# USB_connnection.net
KiCad netlist of a schematic drawn in Altium Designer
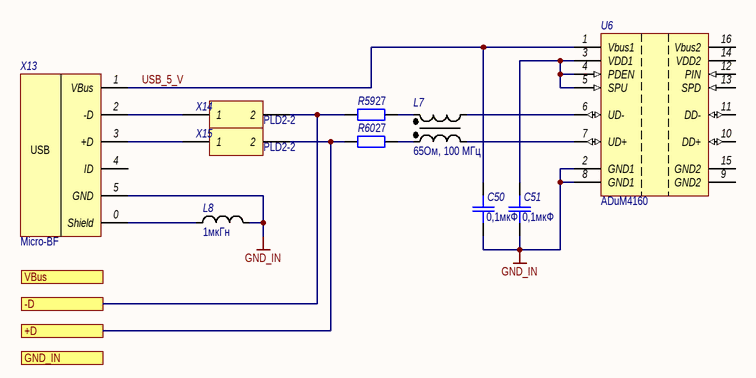
[diagram p0: USB_connnection.SchDoc]

(export (version "E")
  (design (tool "Eeschema 10.0.6"))
  (components
    (comp (ref "C50")
      (value "0,1мкФ")
      (footprint "SMD_0805")
      (description "Capacitor")
      (libsource (lib "Passive") (part "Capacitor"))
    )
    (comp (ref "C51")
      (value "0,1мкФ")
      (footprint "SMD_0805")
      (description "Capacitor")
      (libsource (lib "Passive") (part "Capacitor"))
    )
    (comp (ref "L7")
      (value "65Ом, 100 МГц")
      (footprint "ACM2012")
      (description "Coupled inductor")
      (libsource (lib "Passive") (part "Inductor_coupled"))
    )
    (comp (ref "L8")
      (value "1мкГн")
      (footprint "SMD_0805")
      (description "Inductor")
      (libsource (lib "Passive") (part "Inductor"))
    )
    (comp (ref "R59")
      (value "27")
      (footprint "SMD_0805")
      (description "Resistor")
      (libsource (lib "Passive") (part "Resistor"))
    )
    (comp (ref "R60")
      (value "27")
      (footprint "SMD_0805")
      (description "Resistor")
      (libsource (lib "Passive") (part "Resistor"))
    )
    (comp (ref "U6")
      (value "ADuM1402")
      (footprint "SOIC-16-WIDE")
      (description "Quad Channel Digital Isolator, 2.5 KV rms Insulation Rating")
      (fields (field (name "НАИМЕНОВАНИЕ") "ADuM4160"))
      (libsource (lib "ADuM4160") (part "ADuM4160"))
    )
    (comp (ref "X13")
      (value "mico-BF")
      (footprint "USB Micro-BF")
      (description "USB mico-BF")
      (fields (field (name "НАИМЕНОВАНИЕ") "Micro-BF"))
      (libsource (lib "Connector") (part "MicroUSB"))
    )
    (comp (ref "X14")
      (value "Header 2X1")
      (footprint "PLD2-20")
      (description "Header, 12-Pin, Dual row")
      (fields (field (name "НАИМЕНОВАНИЕ") "PLD2-2"))
      (libsource (lib "Connector") (part "HDR2X1"))
    )
    (comp (ref "X15")
      (value "Header 2X1")
      (footprint "PLD2-20")
      (description "Header, 12-Pin, Dual row")
      (fields (field (name "НАИМЕНОВАНИЕ") "PLD2-2"))
      (libsource (lib "Connector") (part "HDR2X1"))
    )
  )
  (nets
    (net (code "1") (name "/+D") (class "Default")
      (node (ref "R60") (pin "1") (pinfunction "1_1") (pintype "passive"))
      (node (ref "X15") (pin "2") (pinfunction "2_2") (pintype "passive"))
    )
    (net (code "2") (name "/-D") (class "Default")
      (node (ref "R59") (pin "1") (pinfunction "1_1") (pintype "passive"))
      (node (ref "X14") (pin "2") (pinfunction "2_2") (pintype "passive"))
    )
    (net (code "3") (name "/USB_5_V") (class "Default")
      (node (ref "C50") (pin "2") (pinfunction "2_2") (pintype "passive"))
      (node (ref "U6") (pin "1") (pinfunction "Vbus1_1") (pintype "power_in"))
      (node (ref "X13") (pin "1") (pinfunction "VBus_1") (pintype "passive"))
    )
    (net (code "5") (name "GND_IN") (class "Default")
      (node (ref "C50") (pin "1") (pinfunction "1_1") (pintype "passive"))
      (node (ref "C51") (pin "1") (pinfunction "1_1") (pintype "passive"))
      (node (ref "L8") (pin "2") (pinfunction "2_2") (pintype "passive"))
      (node (ref "U6") (pin "2") (pinfunction "GND1_2") (pintype "power_in"))
      (node (ref "U6") (pin "8") (pinfunction "GND1_8") (pintype "power_in"))
      (node (ref "X13") (pin "5") (pinfunction "GND_5") (pintype "passive"))
    )
    (net (code "6") (name "Net-(L7-Pad2)") (class "Default")
      (node (ref "L7") (pin "2") (pinfunction "2_2") (pintype "passive"))
      (node (ref "R60") (pin "2") (pinfunction "2_2") (pintype "passive"))
    )
    (net (code "7") (name "Net-(L7-Pad3)") (class "Default")
      (node (ref "L7") (pin "3") (pinfunction "3_3") (pintype "passive"))
      (node (ref "R59") (pin "2") (pinfunction "2_2") (pintype "passive"))
    )
    (net (code "8") (name "Net-(U6-PDEN)") (class "Default")
      (node (ref "C51") (pin "2") (pinfunction "2_2") (pintype "passive"))
      (node (ref "U6") (pin "3") (pinfunction "VDD1_3") (pintype "power_in"))
      (node (ref "U6") (pin "4") (pinfunction "PDEN_4") (pintype "input"))
      (node (ref "U6") (pin "5") (pinfunction "SPU_5") (pintype "input"))
    )
    (net (code "9") (name "Net-(U6-UD+)") (class "Default")
      (node (ref "L7") (pin "1") (pinfunction "1_1") (pintype "passive"))
      (node (ref "U6") (pin "7") (pinfunction "UD+_7") (pintype "bidirectional"))
    )
    (net (code "10") (name "Net-(U6-UD-)") (class "Default")
      (node (ref "L7") (pin "4") (pinfunction "4_4") (pintype "passive"))
      (node (ref "U6") (pin "6") (pinfunction "UD-_6") (pintype "bidirectional"))
    )
    (net (code "11") (name "Net-(X13-+D)") (class "Default")
      (node (ref "X13") (pin "3") (pinfunction "+D_3") (pintype "passive"))
      (node (ref "X15") (pin "1") (pinfunction "1_1") (pintype "passive"))
    )
    (net (code "12") (name "Net-(X13--D)") (class "Default")
      (node (ref "X13") (pin "2") (pinfunction "-D_2") (pintype "passive"))
      (node (ref "X14") (pin "1") (pinfunction "1_1") (pintype "passive"))
    )
    (net (code "13") (name "Net-(X13-Shield)") (class "Default")
      (node (ref "L8") (pin "1") (pinfunction "1_1") (pintype "passive"))
      (node (ref "X13") (pin "0") (pinfunction "Shield_0") (pintype "passive"))
    )
    (net (code "14") (name "unconnected-(U6-DD+-Pad10)") (class "Default")
      (node (ref "U6") (pin "10") (pinfunction "DD+_10") (pintype "bidirectional"))
    )
    (net (code "15") (name "unconnected-(U6-DD--Pad11)") (class "Default")
      (node (ref "U6") (pin "11") (pinfunction "DD-_11") (pintype "bidirectional"))
    )
    (net (code "16") (name "unconnected-(U6-GND2-Pad9)") (class "Default")
      (node (ref "U6") (pin "9") (pinfunction "GND2_9") (pintype "power_in"))
    )
    (net (code "17") (name "unconnected-(U6-GND2-Pad15)") (class "Default")
      (node (ref "U6") (pin "15") (pinfunction "GND2_15") (pintype "power_in"))
    )
    (net (code "18") (name "unconnected-(U6-PIN-Pad12)") (class "Default")
      (node (ref "U6") (pin "12") (pinfunction "PIN_12") (pintype "input"))
    )
    (net (code "19") (name "unconnected-(U6-SPD-Pad13)") (class "Default")
      (node (ref "U6") (pin "13") (pinfunction "SPD_13") (pintype "input"))
    )
    (net (code "20") (name "unconnected-(U6-VDD2-Pad14)") (class "Default")
      (node (ref "U6") (pin "14") (pinfunction "VDD2_14") (pintype "power_in"))
    )
    (net (code "21") (name "unconnected-(U6-Vbus2-Pad16)") (class "Default")
      (node (ref "U6") (pin "16") (pinfunction "Vbus2_16") (pintype "power_in"))
    )
    (net (code "22") (name "unconnected-(X13-ID-Pad4)") (class "Default")
      (node (ref "X13") (pin "4") (pinfunction "ID_4") (pintype "passive"))
    )
  )
)
